# proximal.net
KiCad netlist of a schematic drawn in Altium Designer
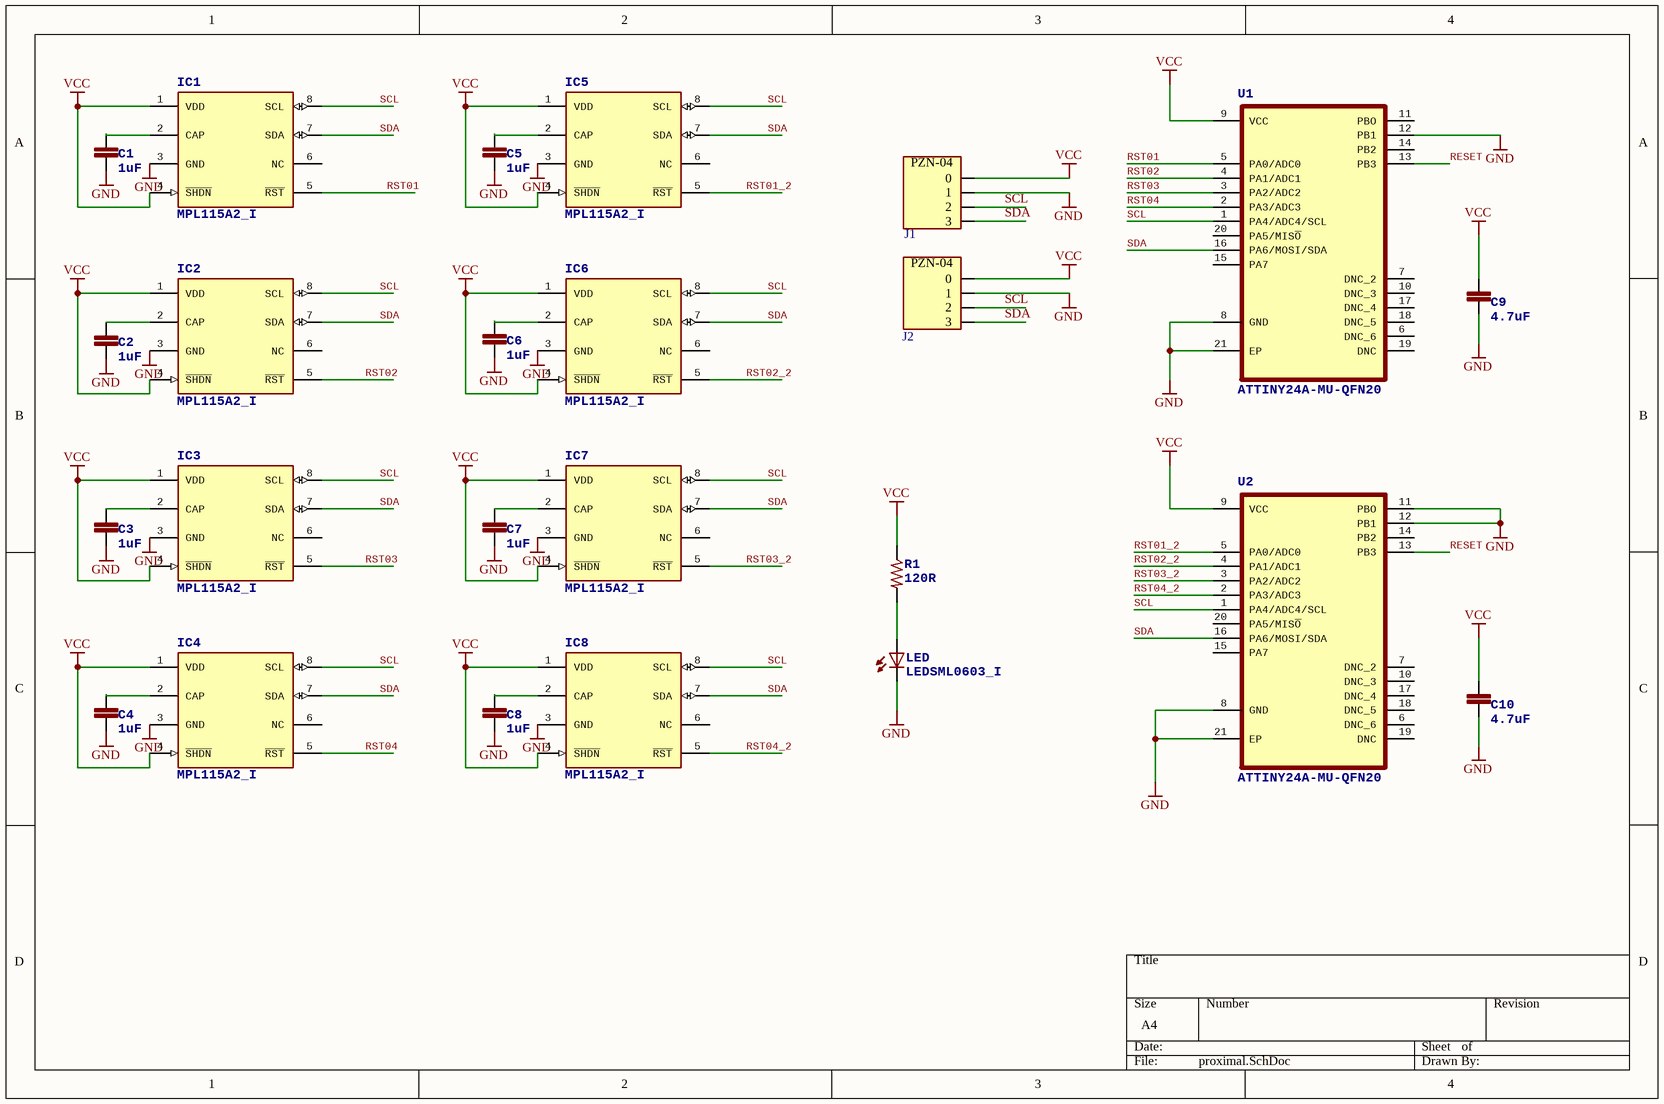
[diagram p0: proximal.SchDoc]

(export (version "E")
  (design (tool "Eeschema 10.0.6"))
  (components
    (comp (ref "C1")
      (value "1uF")
      (footprint "C0402")
      (description "Capacitor - Imperial Units")
      (libsource (lib "rmelo19-library") (part "C0402_I"))
    )
    (comp (ref "C2")
      (value "1uF")
      (footprint "C0402")
      (description "Capacitor - Imperial Units")
      (libsource (lib "rmelo19-library") (part "C0402_I"))
    )
    (comp (ref "C3")
      (value "1uF")
      (footprint "C0402")
      (description "Capacitor - Imperial Units")
      (libsource (lib "rmelo19-library") (part "C0402_I"))
    )
    (comp (ref "C4")
      (value "1uF")
      (footprint "C0402")
      (description "Capacitor - Imperial Units")
      (libsource (lib "rmelo19-library") (part "C0402_I"))
    )
    (comp (ref "C5")
      (value "1uF")
      (footprint "C0402")
      (description "Capacitor - Imperial Units")
      (libsource (lib "rmelo19-library") (part "C0402_I"))
    )
    (comp (ref "C6")
      (value "1uF")
      (footprint "C0402")
      (description "Capacitor - Imperial Units")
      (libsource (lib "rmelo19-library") (part "C0402_I"))
    )
    (comp (ref "C7")
      (value "1uF")
      (footprint "C0402")
      (description "Capacitor - Imperial Units")
      (libsource (lib "rmelo19-library") (part "C0402_I"))
    )
    (comp (ref "C8")
      (value "1uF")
      (footprint "C0402")
      (description "Capacitor - Imperial Units")
      (libsource (lib "rmelo19-library") (part "C0402_I"))
    )
    (comp (ref "C9")
      (value "4.7uF")
      (footprint "C0402")
      (description "CAPACITOR, European symbol")
      (libsource (lib "board") (part "C-EUC0402"))
    )
    (comp (ref "C10")
      (value "4.7uF")
      (footprint "C0402")
      (description "CAPACITOR, European symbol")
      (libsource (lib "board") (part "C-EUC0402"))
    )
    (comp (ref "IC1")
      (value "MPL115A2_I")
      (footprint "MPL115A2")
      (description "Barometer - Imperial Units")
      (libsource (lib "rmelo19-library") (part "MPL115A2_I"))
    )
    (comp (ref "IC2")
      (value "MPL115A2_I")
      (footprint "MPL115A2")
      (description "Barometer - Imperial Units")
      (libsource (lib "rmelo19-library") (part "MPL115A2_I"))
    )
    (comp (ref "IC3")
      (value "MPL115A2_I")
      (footprint "MPL115A2")
      (description "Barometer - Imperial Units")
      (libsource (lib "rmelo19-library") (part "MPL115A2_I"))
    )
    (comp (ref "IC4")
      (value "MPL115A2_I")
      (footprint "MPL115A2")
      (description "Barometer - Imperial Units")
      (libsource (lib "rmelo19-library") (part "MPL115A2_I"))
    )
    (comp (ref "IC5")
      (value "MPL115A2_I")
      (footprint "MPL115A2")
      (description "Barometer - Imperial Units")
      (libsource (lib "rmelo19-library") (part "MPL115A2_I"))
    )
    (comp (ref "IC6")
      (value "MPL115A2_I")
      (footprint "MPL115A2")
      (description "Barometer - Imperial Units")
      (libsource (lib "rmelo19-library") (part "MPL115A2_I"))
    )
    (comp (ref "IC7")
      (value "MPL115A2_I")
      (footprint "MPL115A2")
      (description "Barometer - Imperial Units")
      (libsource (lib "rmelo19-library") (part "MPL115A2_I"))
    )
    (comp (ref "IC8")
      (value "MPL115A2_I")
      (footprint "MPL115A2")
      (description "Barometer - Imperial Units")
      (libsource (lib "rmelo19-library") (part "MPL115A2_I"))
    )
    (comp (ref "J1")
      (value "PZN-04_I")
      (footprint "PZN-04-VV")
      (description "Omnetics PTN Connector 4 pins, Horizontal, Design 1 - Imperial Units")
      (libsource (lib "rmelo19-library") (part "PZN-04_I"))
    )
    (comp (ref "J2")
      (value "PZN-04_I")
      (footprint "PZN-04-VV")
      (description "Omnetics PTN Connector 4 pins, Horizontal, Design 1 - Imperial Units")
      (libsource (lib "rmelo19-library") (part "PZN-04_I"))
    )
    (comp (ref "LED")
      (value "LEDSML0603_I")
      (footprint "SML0603")
      (libsource (lib "rmelo19-library") (part "LEDSML0603_I"))
    )
    (comp (ref "R1")
      (value "120R")
      (footprint "R0402")
      (description "Resistor - Imperial Units")
      (libsource (lib "rmelo19-library") (part "R0402_I"))
    )
    (comp (ref "U1")
      (value "ATTINY24A-MU-QFN20")
      (footprint "QFN50P400X400X80-21N")
      (description "Microcontroller - Imperial Units")
      (fields (field (name "MPN") "ATTINY24A-MU"))
      (libsource (lib "rmelo19-library") (part "ATTINY24A-MU_I"))
    )
    (comp (ref "U2")
      (value "ATTINY24A-MU-QFN20")
      (footprint "QFN50P400X400X80-21N")
      (description "Microcontroller - Imperial Units")
      (fields (field (name "MPN") "ATTINY24A-MU"))
      (libsource (lib "rmelo19-library") (part "ATTINY24A-MU_I"))
    )
  )
  (nets
    (net (code "1") (name "/RESET") (class "Default")
      (node (ref "U1") (pin "13") (pinfunction "PB3_13") (pintype "passive"))
      (node (ref "U2") (pin "13") (pinfunction "PB3_13") (pintype "passive"))
    )
    (net (code "2") (name "/RST01") (class "Default")
      (node (ref "IC1") (pin "5") (pinfunction "~{RST}_5") (pintype "passive"))
      (node (ref "U1") (pin "5") (pinfunction "PA0/ADC0_5") (pintype "passive"))
    )
    (net (code "3") (name "/RST01_2") (class "Default")
      (node (ref "IC5") (pin "5") (pinfunction "~{RST}_5") (pintype "passive"))
      (node (ref "U2") (pin "5") (pinfunction "PA0/ADC0_5") (pintype "passive"))
    )
    (net (code "4") (name "/RST02") (class "Default")
      (node (ref "IC2") (pin "5") (pinfunction "~{RST}_5") (pintype "passive"))
      (node (ref "U1") (pin "4") (pinfunction "PA1/ADC1_4") (pintype "passive"))
    )
    (net (code "5") (name "/RST02_2") (class "Default")
      (node (ref "IC6") (pin "5") (pinfunction "~{RST}_5") (pintype "passive"))
      (node (ref "U2") (pin "4") (pinfunction "PA1/ADC1_4") (pintype "passive"))
    )
    (net (code "6") (name "/RST03") (class "Default")
      (node (ref "IC3") (pin "5") (pinfunction "~{RST}_5") (pintype "passive"))
      (node (ref "U1") (pin "3") (pinfunction "PA2/ADC2_3") (pintype "passive"))
    )
    (net (code "7") (name "/RST03_2") (class "Default")
      (node (ref "IC7") (pin "5") (pinfunction "~{RST}_5") (pintype "passive"))
      (node (ref "U2") (pin "3") (pinfunction "PA2/ADC2_3") (pintype "passive"))
    )
    (net (code "8") (name "/RST04") (class "Default")
      (node (ref "IC4") (pin "5") (pinfunction "~{RST}_5") (pintype "passive"))
      (node (ref "U1") (pin "2") (pinfunction "PA3/ADC3_2") (pintype "passive"))
    )
    (net (code "9") (name "/RST04_2") (class "Default")
      (node (ref "IC8") (pin "5") (pinfunction "~{RST}_5") (pintype "passive"))
      (node (ref "U2") (pin "2") (pinfunction "PA3/ADC3_2") (pintype "passive"))
    )
    (net (code "10") (name "/SCL") (class "Default")
      (node (ref "IC1") (pin "8") (pinfunction "SCL_8") (pintype "bidirectional"))
      (node (ref "IC2") (pin "8") (pinfunction "SCL_8") (pintype "bidirectional"))
      (node (ref "IC3") (pin "8") (pinfunction "SCL_8") (pintype "bidirectional"))
      (node (ref "IC4") (pin "8") (pinfunction "SCL_8") (pintype "bidirectional"))
      (node (ref "IC5") (pin "8") (pinfunction "SCL_8") (pintype "bidirectional"))
      (node (ref "IC6") (pin "8") (pinfunction "SCL_8") (pintype "bidirectional"))
      (node (ref "IC7") (pin "8") (pinfunction "SCL_8") (pintype "bidirectional"))
      (node (ref "IC8") (pin "8") (pinfunction "SCL_8") (pintype "bidirectional"))
      (node (ref "J1") (pin "2") (pinfunction "2_2") (pintype "passive"))
      (node (ref "J2") (pin "2") (pinfunction "2_2") (pintype "passive"))
      (node (ref "U1") (pin "1") (pinfunction "PA4/ADC4/SCL_1") (pintype "passive"))
      (node (ref "U2") (pin "1") (pinfunction "PA4/ADC4/SCL_1") (pintype "passive"))
    )
    (net (code "11") (name "/SDA") (class "Default")
      (node (ref "IC1") (pin "7") (pinfunction "SDA_7") (pintype "bidirectional"))
      (node (ref "IC2") (pin "7") (pinfunction "SDA_7") (pintype "bidirectional"))
      (node (ref "IC3") (pin "7") (pinfunction "SDA_7") (pintype "bidirectional"))
      (node (ref "IC4") (pin "7") (pinfunction "SDA_7") (pintype "bidirectional"))
      (node (ref "IC5") (pin "7") (pinfunction "SDA_7") (pintype "bidirectional"))
      (node (ref "IC6") (pin "7") (pinfunction "SDA_7") (pintype "bidirectional"))
      (node (ref "IC7") (pin "7") (pinfunction "SDA_7") (pintype "bidirectional"))
      (node (ref "IC8") (pin "7") (pinfunction "SDA_7") (pintype "bidirectional"))
      (node (ref "J1") (pin "3") (pinfunction "3_3") (pintype "passive"))
      (node (ref "J2") (pin "3") (pinfunction "3_3") (pintype "passive"))
      (node (ref "U1") (pin "16") (pinfunction "PA6/MOSI/SDA_16") (pintype "passive"))
      (node (ref "U2") (pin "16") (pinfunction "PA6/MOSI/SDA_16") (pintype "passive"))
    )
    (net (code "12") (name "GND") (class "Default")
      (node (ref "C1") (pin "2") (pinfunction "2_2") (pintype "passive"))
      (node (ref "C10") (pin "2") (pinfunction "2_2") (pintype "passive"))
      (node (ref "C2") (pin "2") (pinfunction "2_2") (pintype "passive"))
      (node (ref "C3") (pin "2") (pinfunction "2_2") (pintype "passive"))
      (node (ref "C4") (pin "2") (pinfunction "2_2") (pintype "passive"))
      (node (ref "C5") (pin "2") (pinfunction "2_2") (pintype "passive"))
      (node (ref "C6") (pin "2") (pinfunction "2_2") (pintype "passive"))
      (node (ref "C7") (pin "2") (pinfunction "2_2") (pintype "passive"))
      (node (ref "C8") (pin "2") (pinfunction "2_2") (pintype "passive"))
      (node (ref "C9") (pin "2") (pinfunction "2_2") (pintype "passive"))
      (node (ref "IC1") (pin "3") (pinfunction "GND_3") (pintype "power_in"))
      (node (ref "IC2") (pin "3") (pinfunction "GND_3") (pintype "power_in"))
      (node (ref "IC3") (pin "3") (pinfunction "GND_3") (pintype "power_in"))
      (node (ref "IC4") (pin "3") (pinfunction "GND_3") (pintype "power_in"))
      (node (ref "IC5") (pin "3") (pinfunction "GND_3") (pintype "power_in"))
      (node (ref "IC6") (pin "3") (pinfunction "GND_3") (pintype "power_in"))
      (node (ref "IC7") (pin "3") (pinfunction "GND_3") (pintype "power_in"))
      (node (ref "IC8") (pin "3") (pinfunction "GND_3") (pintype "power_in"))
      (node (ref "J1") (pin "1") (pinfunction "1_1") (pintype "passive"))
      (node (ref "J2") (pin "1") (pinfunction "1_1") (pintype "passive"))
      (node (ref "LED") (pin "C") (pinfunction "C_C") (pintype "passive"))
      (node (ref "U1") (pin "12") (pinfunction "PB1_12") (pintype "passive"))
      (node (ref "U1") (pin "21") (pinfunction "EP_21") (pintype "passive"))
      (node (ref "U1") (pin "8") (pinfunction "GND_8") (pintype "power_in"))
      (node (ref "U2") (pin "11") (pinfunction "PBO_11") (pintype "passive"))
      (node (ref "U2") (pin "12") (pinfunction "PB1_12") (pintype "passive"))
      (node (ref "U2") (pin "21") (pinfunction "EP_21") (pintype "passive"))
      (node (ref "U2") (pin "8") (pinfunction "GND_8") (pintype "power_in"))
    )
    (net (code "13") (name "Net-(IC1-CAP)") (class "Default")
      (node (ref "C1") (pin "1") (pinfunction "1_1") (pintype "passive"))
      (node (ref "IC1") (pin "2") (pinfunction "CAP_2") (pintype "passive"))
    )
    (net (code "14") (name "Net-(IC2-CAP)") (class "Default")
      (node (ref "C2") (pin "1") (pinfunction "1_1") (pintype "passive"))
      (node (ref "IC2") (pin "2") (pinfunction "CAP_2") (pintype "passive"))
    )
    (net (code "15") (name "Net-(IC3-CAP)") (class "Default")
      (node (ref "C3") (pin "1") (pinfunction "1_1") (pintype "passive"))
      (node (ref "IC3") (pin "2") (pinfunction "CAP_2") (pintype "passive"))
    )
    (net (code "16") (name "Net-(IC4-CAP)") (class "Default")
      (node (ref "C4") (pin "1") (pinfunction "1_1") (pintype "passive"))
      (node (ref "IC4") (pin "2") (pinfunction "CAP_2") (pintype "passive"))
    )
    (net (code "17") (name "Net-(IC5-CAP)") (class "Default")
      (node (ref "C5") (pin "1") (pinfunction "1_1") (pintype "passive"))
      (node (ref "IC5") (pin "2") (pinfunction "CAP_2") (pintype "passive"))
    )
    (net (code "18") (name "Net-(IC6-CAP)") (class "Default")
      (node (ref "C6") (pin "1") (pinfunction "1_1") (pintype "passive"))
      (node (ref "IC6") (pin "2") (pinfunction "CAP_2") (pintype "passive"))
    )
    (net (code "19") (name "Net-(IC7-CAP)") (class "Default")
      (node (ref "C7") (pin "1") (pinfunction "1_1") (pintype "passive"))
      (node (ref "IC7") (pin "2") (pinfunction "CAP_2") (pintype "passive"))
    )
    (net (code "20") (name "Net-(IC8-CAP)") (class "Default")
      (node (ref "C8") (pin "1") (pinfunction "1_1") (pintype "passive"))
      (node (ref "IC8") (pin "2") (pinfunction "CAP_2") (pintype "passive"))
    )
    (net (code "21") (name "Net-(LED-PadA)") (class "Default")
      (node (ref "LED") (pin "A") (pinfunction "A_A") (pintype "passive"))
      (node (ref "R1") (pin "1") (pinfunction "1_1") (pintype "passive"))
    )
    (net (code "22") (name "VCC") (class "Default")
      (node (ref "C10") (pin "1") (pinfunction "1_1") (pintype "passive"))
      (node (ref "C9") (pin "1") (pinfunction "1_1") (pintype "passive"))
      (node (ref "IC1") (pin "1") (pinfunction "VDD_1") (pintype "power_in"))
      (node (ref "IC1") (pin "4") (pinfunction "~{SHDN}_4") (pintype "input"))
      (node (ref "IC2") (pin "1") (pinfunction "VDD_1") (pintype "power_in"))
      (node (ref "IC2") (pin "4") (pinfunction "~{SHDN}_4") (pintype "input"))
      (node (ref "IC3") (pin "1") (pinfunction "VDD_1") (pintype "power_in"))
      (node (ref "IC3") (pin "4") (pinfunction "~{SHDN}_4") (pintype "input"))
      (node (ref "IC4") (pin "1") (pinfunction "VDD_1") (pintype "power_in"))
      (node (ref "IC4") (pin "4") (pinfunction "~{SHDN}_4") (pintype "input"))
      (node (ref "IC5") (pin "1") (pinfunction "VDD_1") (pintype "power_in"))
      (node (ref "IC5") (pin "4") (pinfunction "~{SHDN}_4") (pintype "input"))
      (node (ref "IC6") (pin "1") (pinfunction "VDD_1") (pintype "power_in"))
      (node (ref "IC6") (pin "4") (pinfunction "~{SHDN}_4") (pintype "input"))
      (node (ref "IC7") (pin "1") (pinfunction "VDD_1") (pintype "power_in"))
      (node (ref "IC7") (pin "4") (pinfunction "~{SHDN}_4") (pintype "input"))
      (node (ref "IC8") (pin "1") (pinfunction "VDD_1") (pintype "power_in"))
      (node (ref "IC8") (pin "4") (pinfunction "~{SHDN}_4") (pintype "input"))
      (node (ref "J1") (pin "0") (pinfunction "0_0") (pintype "passive"))
      (node (ref "J2") (pin "0") (pinfunction "0_0") (pintype "passive"))
      (node (ref "R1") (pin "2") (pinfunction "2_2") (pintype "passive"))
      (node (ref "U1") (pin "9") (pinfunction "VCC_9") (pintype "power_in"))
      (node (ref "U2") (pin "9") (pinfunction "VCC_9") (pintype "power_in"))
    )
    (net (code "23") (name "unconnected-(IC1-NC-Pad6)") (class "Default")
      (node (ref "IC1") (pin "6") (pinfunction "NC_6") (pintype "passive"))
    )
    (net (code "24") (name "unconnected-(IC2-NC-Pad6)") (class "Default")
      (node (ref "IC2") (pin "6") (pinfunction "NC_6") (pintype "passive"))
    )
    (net (code "25") (name "unconnected-(IC3-NC-Pad6)") (class "Default")
      (node (ref "IC3") (pin "6") (pinfunction "NC_6") (pintype "passive"))
    )
    (net (code "26") (name "unconnected-(IC4-NC-Pad6)") (class "Default")
      (node (ref "IC4") (pin "6") (pinfunction "NC_6") (pintype "passive"))
    )
    (net (code "27") (name "unconnected-(IC5-NC-Pad6)") (class "Default")
      (node (ref "IC5") (pin "6") (pinfunction "NC_6") (pintype "passive"))
    )
    (net (code "28") (name "unconnected-(IC6-NC-Pad6)") (class "Default")
      (node (ref "IC6") (pin "6") (pinfunction "NC_6") (pintype "passive"))
    )
    (net (code "29") (name "unconnected-(IC7-NC-Pad6)") (class "Default")
      (node (ref "IC7") (pin "6") (pinfunction "NC_6") (pintype "passive"))
    )
    (net (code "30") (name "unconnected-(IC8-NC-Pad6)") (class "Default")
      (node (ref "IC8") (pin "6") (pinfunction "NC_6") (pintype "passive"))
    )
    (net (code "31") (name "unconnected-(U1-DNC-Pad19)") (class "Default")
      (node (ref "U1") (pin "19") (pinfunction "DNC_19") (pintype "passive"))
    )
    (net (code "32") (name "unconnected-(U1-DNC_2-Pad7)") (class "Default")
      (node (ref "U1") (pin "7") (pinfunction "DNC_2_7") (pintype "passive"))
    )
    (net (code "33") (name "unconnected-(U1-DNC_3-Pad10)") (class "Default")
      (node (ref "U1") (pin "10") (pinfunction "DNC_3_10") (pintype "passive"))
    )
    (net (code "34") (name "unconnected-(U1-DNC_4-Pad17)") (class "Default")
      (node (ref "U1") (pin "17") (pinfunction "DNC_4_17") (pintype "passive"))
    )
    (net (code "35") (name "unconnected-(U1-DNC_5-Pad18)") (class "Default")
      (node (ref "U1") (pin "18") (pinfunction "DNC_5_18") (pintype "passive"))
    )
    (net (code "36") (name "unconnected-(U1-DNC_6-Pad6)") (class "Default")
      (node (ref "U1") (pin "6") (pinfunction "DNC_6_6") (pintype "passive"))
    )
    (net (code "37") (name "unconnected-(U1-PA5{slash}MIS~{O}-Pad20)") (class "Default")
      (node (ref "U1") (pin "20") (pinfunction "PA5/MIS~{O}_20") (pintype "passive"))
    )
    (net (code "38") (name "unconnected-(U1-PA7-Pad15)") (class "Default")
      (node (ref "U1") (pin "15") (pinfunction "PA7_15") (pintype "passive"))
    )
    (net (code "39") (name "unconnected-(U1-PB2-Pad14)") (class "Default")
      (node (ref "U1") (pin "14") (pinfunction "PB2_14") (pintype "passive"))
    )
    (net (code "40") (name "unconnected-(U1-PBO-Pad11)") (class "Default")
      (node (ref "U1") (pin "11") (pinfunction "PBO_11") (pintype "passive"))
    )
    (net (code "41") (name "unconnected-(U2-DNC-Pad19)") (class "Default")
      (node (ref "U2") (pin "19") (pinfunction "DNC_19") (pintype "passive"))
    )
    (net (code "42") (name "unconnected-(U2-DNC_2-Pad7)") (class "Default")
      (node (ref "U2") (pin "7") (pinfunction "DNC_2_7") (pintype "passive"))
    )
    (net (code "43") (name "unconnected-(U2-DNC_3-Pad10)") (class "Default")
      (node (ref "U2") (pin "10") (pinfunction "DNC_3_10") (pintype "passive"))
    )
    (net (code "44") (name "unconnected-(U2-DNC_4-Pad17)") (class "Default")
      (node (ref "U2") (pin "17") (pinfunction "DNC_4_17") (pintype "passive"))
    )
    (net (code "45") (name "unconnected-(U2-DNC_5-Pad18)") (class "Default")
      (node (ref "U2") (pin "18") (pinfunction "DNC_5_18") (pintype "passive"))
    )
    (net (code "46") (name "unconnected-(U2-DNC_6-Pad6)") (class "Default")
      (node (ref "U2") (pin "6") (pinfunction "DNC_6_6") (pintype "passive"))
    )
    (net (code "47") (name "unconnected-(U2-PA5{slash}MIS~{O}-Pad20)") (class "Default")
      (node (ref "U2") (pin "20") (pinfunction "PA5/MIS~{O}_20") (pintype "passive"))
    )
    (net (code "48") (name "unconnected-(U2-PA7-Pad15)") (class "Default")
      (node (ref "U2") (pin "15") (pinfunction "PA7_15") (pintype "passive"))
    )
    (net (code "49") (name "unconnected-(U2-PB2-Pad14)") (class "Default")
      (node (ref "U2") (pin "14") (pinfunction "PB2_14") (pintype "passive"))
    )
  )
)
